# Ethernet.net
KiCad netlist of a schematic drawn in Altium Designer
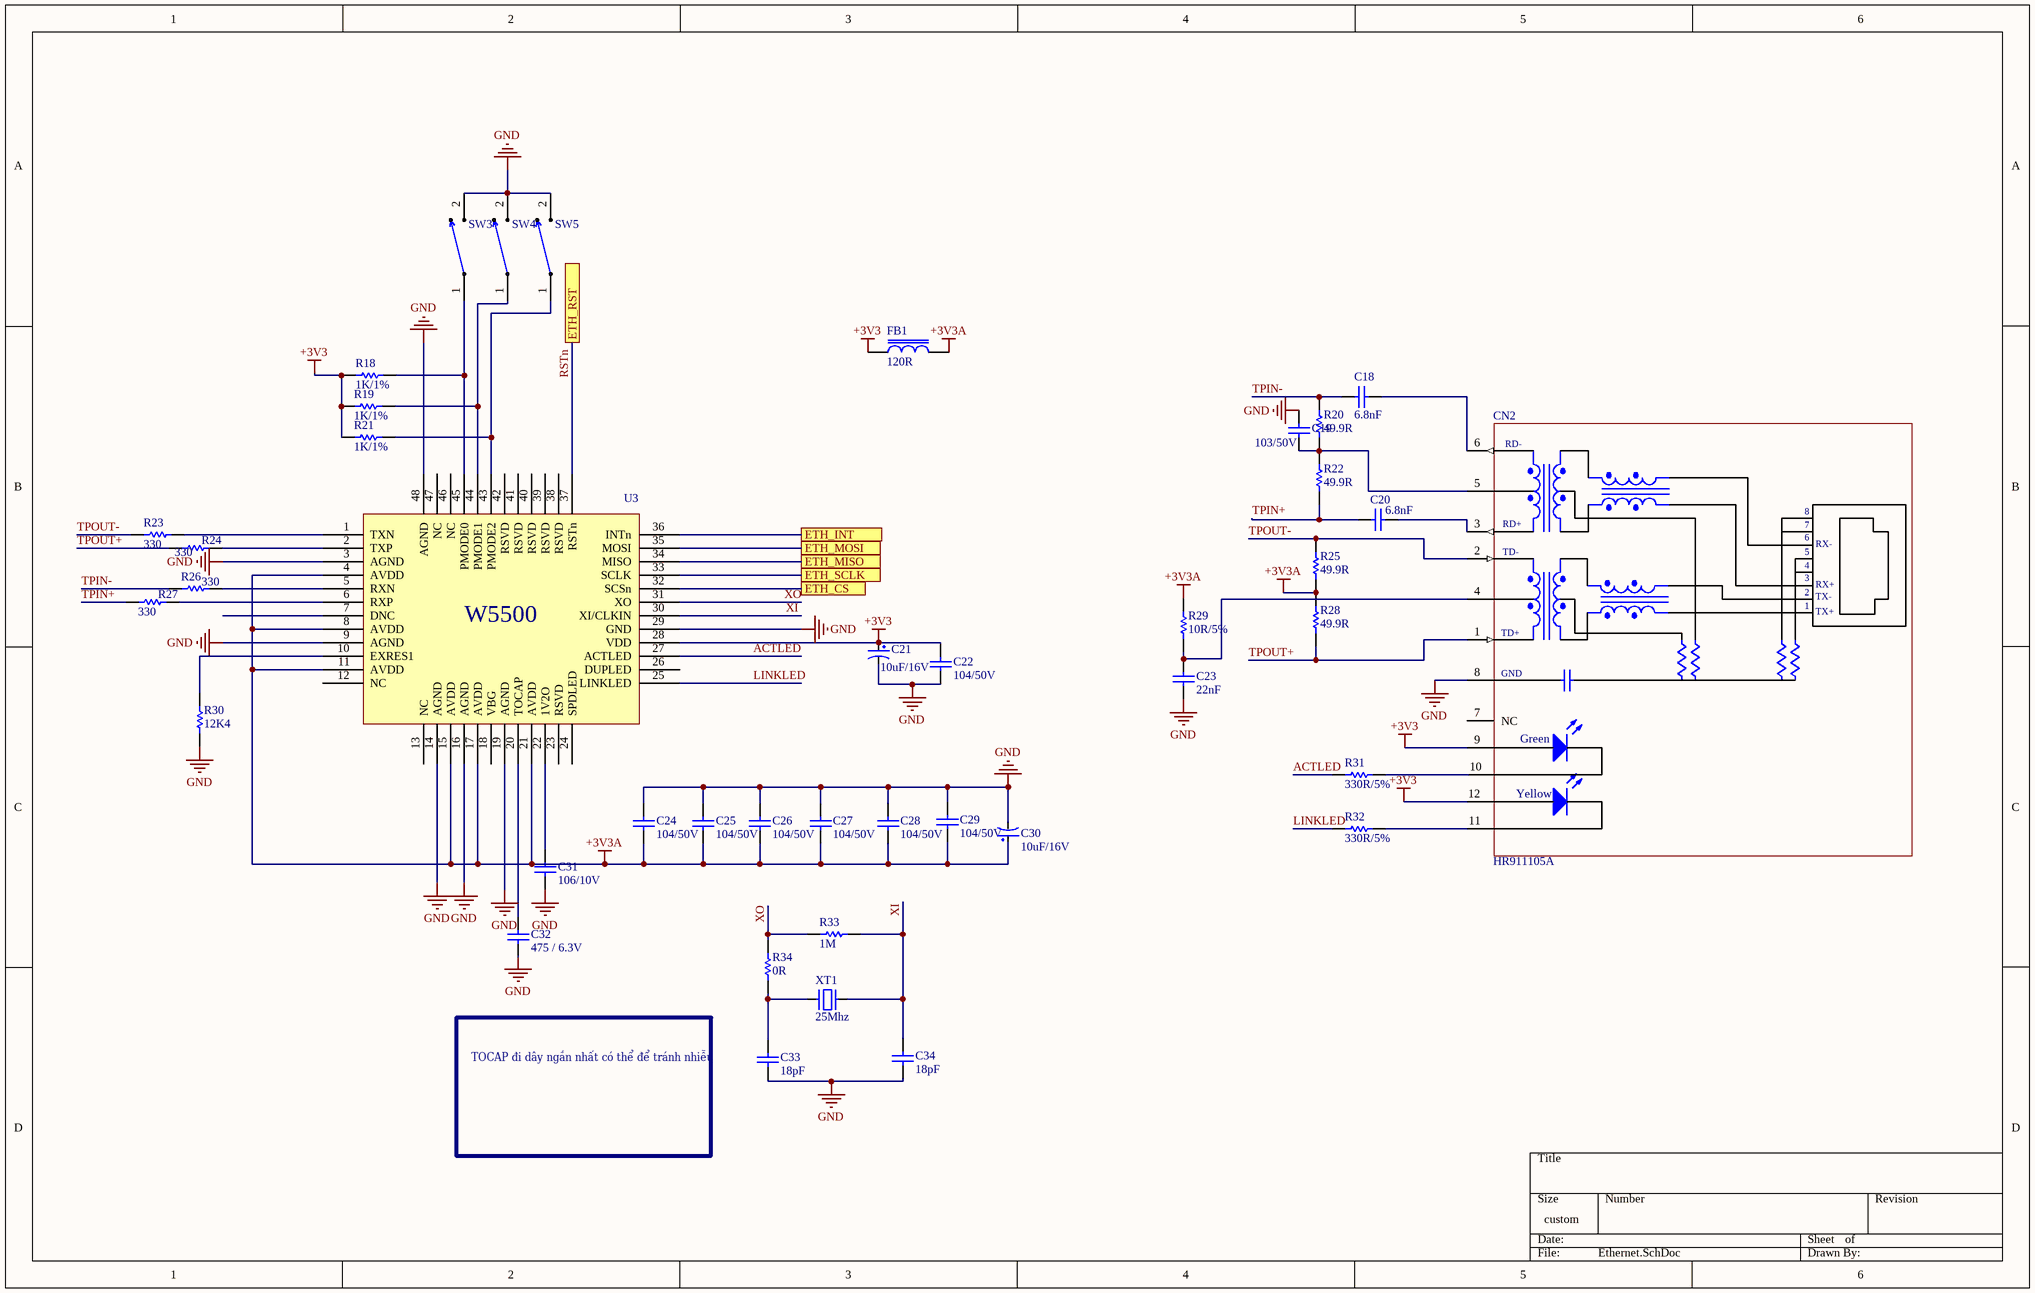
[diagram p0: Ethernet.SchDoc]

(export (version "E")
  (design (tool "Eeschema 10.0.6"))
  (components
    (comp (ref "C18")
      (value "6.8nF")
      (footprint "C0603-B")
      (description "50V 68nF X7R ±10% 0603 Multilayer Ceramic Capacitors MLCC - SMD/SMT ROHS")
      (fields
        (field (name "PARTNUMBER") "CL10B683KB8NNNC")
        (field (name "BSH PARTNUMBER") "C31658")
        (field (name "CREATOR") "Digo")
      )
      (libsource (lib "library-SH") (part "CAP"))
    )
    (comp (ref "C19")
      (value "103/50V")
      (footprint "C0603-B")
      (description "10nF ±10% 50V X7R 0603 Multilayer Ceramic Capacitors MLCC - SMD/SMT RoHS")
      (fields
        (field (name "PARTNUMBER") "CL10B103KB8NNNC")
        (field (name "BSH PARTNUMBER") "C1589")
        (field (name "CREATOR") "Digo")
      )
      (libsource (lib "library-SH") (part "CAP"))
    )
    (comp (ref "C20")
      (value "6.8nF")
      (footprint "C0603-B")
      (description "50V 68nF X7R ±10% 0603 Multilayer Ceramic Capacitors MLCC - SMD/SMT ROHS")
      (fields
        (field (name "PARTNUMBER") "CL10B683KB8NNNC")
        (field (name "BSH PARTNUMBER") "C31658")
        (field (name "CREATOR") "Digo")
      )
      (libsource (lib "library-SH") (part "CAP"))
    )
    (comp (ref "C21")
      (value "10uF/16V")
      (footprint "CAP_3216")
      (description "Polarized Capacitor (Axial)")
      (fields (field (name "PUBLISHER") "Altium Limited"))
      (libsource (lib "My Library") (part "CAP-ALU-SMD"))
    )
    (comp (ref "C22")
      (value "104/50V")
      (footprint "C0603-B")
      (description "100nF ±10% 50V X7R 0603 Multilayer Ceramic Capacitors MLCC - SMD/SMT RoHS")
      (fields
        (field (name "PARTNUMBER") "CL10B104KB8NNNC")
        (field (name "BSH PARTNUMBER") "C1591")
        (field (name "CREATOR") "Digo")
      )
      (libsource (lib "library-SH") (part "CAP"))
    )
    (comp (ref "C23")
      (value "22nF")
      (footprint "C0603-B")
      (description "2.2nF ±10% 50V X7R 0603 Multilayer Ceramic Capacitors MLCC - SMD/SMT RoHS")
      (fields
        (field (name "PARTNUMBER") "CL10B222KB8NNNC")
        (field (name "BSH PARTNUMBER") "C16033")
        (field (name "CREATOR") "Digo")
      )
      (libsource (lib "library-SH") (part "CAP"))
    )
    (comp (ref "C24")
      (value "104/50V")
      (footprint "C0603-B")
      (description "100nF ±10% 50V X7R 0603 Multilayer Ceramic Capacitors MLCC - SMD/SMT RoHS")
      (fields
        (field (name "PARTNUMBER") "CL10B104KB8NNNC")
        (field (name "BSH PARTNUMBER") "C1591")
        (field (name "CREATOR") "Digo")
      )
      (libsource (lib "library-SH") (part "CAP"))
    )
    (comp (ref "C25")
      (value "104/50V")
      (footprint "C0603-B")
      (description "100nF ±10% 50V X7R 0603 Multilayer Ceramic Capacitors MLCC - SMD/SMT RoHS")
      (fields
        (field (name "PARTNUMBER") "CL10B104KB8NNNC")
        (field (name "BSH PARTNUMBER") "C1591")
        (field (name "CREATOR") "Digo")
      )
      (libsource (lib "library-SH") (part "CAP"))
    )
    (comp (ref "C26")
      (value "104/50V")
      (footprint "C0603-B")
      (description "100nF ±10% 50V X7R 0603 Multilayer Ceramic Capacitors MLCC - SMD/SMT RoHS")
      (fields
        (field (name "PARTNUMBER") "CL10B104KB8NNNC")
        (field (name "BSH PARTNUMBER") "C1591")
        (field (name "CREATOR") "Digo")
      )
      (libsource (lib "library-SH") (part "CAP"))
    )
    (comp (ref "C27")
      (value "104/50V")
      (footprint "C0603-B")
      (description "100nF ±10% 50V X7R 0603 Multilayer Ceramic Capacitors MLCC - SMD/SMT RoHS")
      (fields
        (field (name "PARTNUMBER") "CL10B104KB8NNNC")
        (field (name "BSH PARTNUMBER") "C1591")
        (field (name "CREATOR") "Digo")
      )
      (libsource (lib "library-SH") (part "CAP"))
    )
    (comp (ref "C28")
      (value "104/50V")
      (footprint "C0603-B")
      (description "100nF ±10% 50V X7R 0603 Multilayer Ceramic Capacitors MLCC - SMD/SMT RoHS")
      (fields
        (field (name "PARTNUMBER") "CL10B104KB8NNNC")
        (field (name "BSH PARTNUMBER") "C1591")
        (field (name "CREATOR") "Digo")
      )
      (libsource (lib "library-SH") (part "CAP"))
    )
    (comp (ref "C29")
      (value "104/50V")
      (footprint "C0603-B")
      (description "100nF ±10% 50V X7R 0603 Multilayer Ceramic Capacitors MLCC - SMD/SMT RoHS")
      (fields
        (field (name "PARTNUMBER") "CL10B104KB8NNNC")
        (field (name "BSH PARTNUMBER") "C1591")
        (field (name "CREATOR") "Digo")
      )
      (libsource (lib "library-SH") (part "CAP"))
    )
    (comp (ref "C30")
      (value "10uF/16V")
      (footprint "CAP_3216")
      (description "Polarized Capacitor (Axial)")
      (fields (field (name "PUBLISHER") "Altium Limited"))
      (libsource (lib "My Library") (part "CAP-ALU-SMD"))
    )
    (comp (ref "C31")
      (value "106/10V")
      (footprint "C0603-B")
      (description "10uF ±10% 10V X5R 0603 Multilayer Ceramic Capacitors MLCC - SMD/SMT RoHS")
      (fields
        (field (name "PARTNUMBER") "CL10A106KP8NNNC")
        (field (name "BSH PARTNUMBER") "C19702")
        (field (name "CREATOR") "Digo")
      )
      (libsource (lib "library-SH") (part "CAP"))
    )
    (comp (ref "C32")
      (value "475 / 6.3V")
      (footprint "C0603-B")
      (description "Multilayer Ceramic Capacitors MLCC - SMD/SMT 4.7uF+/-20% 6.3V X5R 1608")
      (fields
        (field (name "PARTNUMBER") "CL10A475MQ8NNNC")
        (field (name "BSH PARTNUMBER") "New part")
        (field (name "CREATOR") "NamNH")
      )
      (libsource (lib "library-SH") (part "CAP"))
    )
    (comp (ref "C33")
      (value "18pF")
      (footprint "C0603-B")
      (description "10uF ±10% 10V X5R 0603 Multilayer Ceramic Capacitors MLCC - SMD/SMT RoHS")
      (fields
        (field (name "PARTNUMBER") "CL10A106KP8NNNC")
        (field (name "BSH PARTNUMBER") "C19702")
        (field (name "CREATOR") "Digo")
      )
      (libsource (lib "library-SH") (part "CAP"))
    )
    (comp (ref "C34")
      (value "18pF")
      (footprint "C0603-B")
      (description "10uF ±10% 10V X5R 0603 Multilayer Ceramic Capacitors MLCC - SMD/SMT RoHS")
      (fields
        (field (name "PARTNUMBER") "CL10A106KP8NNNC")
        (field (name "BSH PARTNUMBER") "C19702")
        (field (name "CREATOR") "Digo")
      )
      (libsource (lib "library-SH") (part "CAP"))
    )
    (comp (ref "CN2")
      (value "HR911105A")
      (footprint "HR911105A")
      (description "CON  RJ45  with Magnetics & LED")
      (fields (field (name "BSH PARTNUMBER") "CN-HR911105A") (field (name "CREATOR") "ChienNQ"))
      (libsource (lib "library-SH") (part "HR911105A"))
    )
    (comp (ref "FB1")
      (value "120R")
      (footprint "FB0805-B")
      (description "2A 1 200mΩ 300Ω 100MHz 0805 Ferrite Beads ROHS")
      (fields
        (field (name "PARTNUMBER") "CBW201209U301T")
        (field (name "BSH PARTNUMBER") "C67451")
        (field (name "CREATOR") "Digo")
      )
      (libsource (lib "library-SH") (part "FB"))
    )
    (comp (ref "R18")
      (value "1K/1%")
      (footprint "R0603-B")
      (description "RES 0603 1K 1% 100mW")
      (fields
        (field (name "PARTNUMBER") "RC0603FR-071KL")
        (field (name "BSH PARTNUMBER") "R-1k-0603-1")
        (field (name "CREATOR") "SmartDevice")
      )
      (libsource (lib "library-SH") (part "RES"))
    )
    (comp (ref "R19")
      (value "1K/1%")
      (footprint "R0603-B")
      (description "RES 0603 1K 1% 100mW")
      (fields
        (field (name "PARTNUMBER") "RC0603FR-071KL")
        (field (name "BSH PARTNUMBER") "R-1k-0603-1")
        (field (name "CREATOR") "SmartDevice")
      )
      (libsource (lib "library-SH") (part "RES"))
    )
    (comp (ref "R20")
      (value "49.9R")
      (footprint "R0603-B")
      (description "RES 0603 10K 1% 100mW")
      (fields
        (field (name "PARTNUMBER") "RC0603FR-0710KL")
        (field (name "BSH PARTNUMBER") "C98220")
        (field (name "CREATOR") "Digo")
      )
      (libsource (lib "library-SH") (part "RES"))
    )
    (comp (ref "R21")
      (value "1K/1%")
      (footprint "R0603-B")
      (description "RES 0603 1K 1% 100mW")
      (fields
        (field (name "PARTNUMBER") "RC0603FR-071KL")
        (field (name "BSH PARTNUMBER") "R-1k-0603-1")
        (field (name "CREATOR") "SmartDevice")
      )
      (libsource (lib "library-SH") (part "RES"))
    )
    (comp (ref "R22")
      (value "49.9R")
      (footprint "R0603-B")
      (description "RES 0603 10K 1% 100mW")
      (fields
        (field (name "PARTNUMBER") "RC0603FR-0710KL")
        (field (name "BSH PARTNUMBER") "C98220")
        (field (name "CREATOR") "Digo")
      )
      (libsource (lib "library-SH") (part "RES"))
    )
    (comp (ref "R23")
      (value "330")
      (footprint "R0603-B")
      (description "RES 0603 33R 5% 100mW")
      (fields
        (field (name "PARTNUMBER") "RC0603JR-0733RL")
        (field (name "BSH PARTNUMBER") "R-33R-0603-5")
        (field (name "CREATOR") "ChienNQ")
      )
      (libsource (lib "library-SH") (part "RES"))
    )
    (comp (ref "R24")
      (value "330")
      (footprint "R0603-B")
      (description "RES 0603 33R 5% 100mW")
      (fields
        (field (name "PARTNUMBER") "RC0603JR-0733RL")
        (field (name "BSH PARTNUMBER") "R-33R-0603-5")
        (field (name "CREATOR") "ChienNQ")
      )
      (libsource (lib "library-SH") (part "RES"))
    )
    (comp (ref "R25")
      (value "49.9R")
      (footprint "R0603-B")
      (description "RES 0603 10K 1% 100mW")
      (fields
        (field (name "PARTNUMBER") "RC0603FR-0710KL")
        (field (name "BSH PARTNUMBER") "C98220")
        (field (name "CREATOR") "Digo")
      )
      (libsource (lib "library-SH") (part "RES"))
    )
    (comp (ref "R26")
      (value "330")
      (footprint "R0603-B")
      (description "RES 0603 33R 5% 100mW")
      (fields
        (field (name "PARTNUMBER") "RC0603JR-0733RL")
        (field (name "BSH PARTNUMBER") "R-33R-0603-5")
        (field (name "CREATOR") "ChienNQ")
      )
      (libsource (lib "library-SH") (part "RES"))
    )
    (comp (ref "R27")
      (value "330")
      (footprint "R0603-B")
      (description "RES 0603 33R 5% 100mW")
      (fields
        (field (name "PARTNUMBER") "RC0603JR-0733RL")
        (field (name "BSH PARTNUMBER") "R-33R-0603-5")
        (field (name "CREATOR") "ChienNQ")
      )
      (libsource (lib "library-SH") (part "RES"))
    )
    (comp (ref "R28")
      (value "49.9R")
      (footprint "R0603-B")
      (description "RES 0603 10K 1% 100mW")
      (fields
        (field (name "PARTNUMBER") "RC0603FR-0710KL")
        (field (name "BSH PARTNUMBER") "C98220")
        (field (name "CREATOR") "Digo")
      )
      (libsource (lib "library-SH") (part "RES"))
    )
    (comp (ref "R29")
      (value "10R/5%")
      (footprint "R0603-B")
      (description "RES 0603 10R 5% 100mW")
      (fields
        (field (name "PARTNUMBER") "RC0603JR-0710RL")
        (field (name "BSH PARTNUMBER") "C109317")
        (field (name "CREATOR") "Digo")
      )
      (libsource (lib "library-SH") (part "RES"))
    )
    (comp (ref "R30")
      (value "12K4")
      (footprint "R0603-B")
      (description "RES 0603 12.4K 1% 100mW")
      (fields
        (field (name "PARTNUMBER") "RC0603FR-0712K4L")
        (field (name "BSH PARTNUMBER") "R-12K4-0603-1")
        (field (name "CREATOR") "ChienNQ")
      )
      (libsource (lib "library-SH") (part "RES"))
    )
    (comp (ref "R31")
      (value "330R/5%")
      (footprint "R0603-B")
      (description "RES 0603 330R 5% 100mW")
      (fields
        (field (name "PARTNUMBER") "RC0603JR-07330RL")
        (field (name "BSH PARTNUMBER") "R-330R-0603-5")
        (field (name "CREATOR") "SmartDevice")
      )
      (libsource (lib "library-SH") (part "RES"))
    )
    (comp (ref "R32")
      (value "330R/5%")
      (footprint "R0603-B")
      (description "RES 0603 330R 5% 100mW")
      (fields
        (field (name "PARTNUMBER") "RC0603JR-07330RL")
        (field (name "BSH PARTNUMBER") "R-330R-0603-5")
        (field (name "CREATOR") "SmartDevice")
      )
      (libsource (lib "library-SH") (part "RES"))
    )
    (comp (ref "R33")
      (value "1M")
      (footprint "R0603-B")
      (description "RES 0603 2M 5% 100mW")
      (fields
        (field (name "PARTNUMBER") "RC0603JR-072ML")
        (field (name "BSH PARTNUMBER") "R-2M-0603-5")
        (field (name "CREATOR") "NamNHc")
      )
      (libsource (lib "library-SH") (part "RES"))
    )
    (comp (ref "R34")
      (value "0R")
      (footprint "R0603-B")
      (description "RES 0603 0R 5% 100mW")
      (fields
        (field (name "PARTNUMBER") "RC0603JR-070RL")
        (field (name "BSH PARTNUMBER") "C95177")
        (field (name "CREATOR") "Digo")
      )
      (libsource (lib "library-SH") (part "RES"))
    )
    (comp (ref "SW3")
      (value "Switch NO")
      (footprint "SW0.5 NO")
      (fields
        (field (name "PARTNUMBER") "PCB Switch NO")
        (field (name "BSH PARTNUMBER") "New part")
        (field (name "CREATOR") "NamNH")
      )
      (libsource (lib "library-SH") (part "Switch NO"))
    )
    (comp (ref "SW4")
      (value "Switch NO")
      (footprint "SW0.5 NO")
      (fields
        (field (name "PARTNUMBER") "PCB Switch NO")
        (field (name "BSH PARTNUMBER") "New part")
        (field (name "CREATOR") "NamNH")
      )
      (libsource (lib "library-SH") (part "Switch NO"))
    )
    (comp (ref "SW5")
      (value "Switch NO")
      (footprint "SW0.5 NO")
      (fields
        (field (name "PARTNUMBER") "PCB Switch NO")
        (field (name "BSH PARTNUMBER") "New part")
        (field (name "CREATOR") "NamNH")
      )
      (libsource (lib "library-SH") (part "Switch NO"))
    )
    (comp (ref "U3") (value "W5500") (footprint "LQFP 48") (libsource (lib "My Library") (part "W5500")))
    (comp (ref "XT1")
      (value "25Mhz")
      (footprint "XTAL-RU49/4")
      (description "CRYSTAL 12.0000MHZ 18PF SMD")
      (fields
        (field (name "MANUFACTURER") "IQD Frequency Products")
        (field (name "PART NUMBER") "LFXTAL036356REEL")
      )
      (libsource (lib "My Library") (part "XT2_1"))
    )
  )
  (nets
    (net (code "1") (name "+3V3") (class "Default")
      (node (ref "C21") (pin "1") (pinfunction "1_1") (pintype "passive"))
      (node (ref "C22") (pin "2") (pinfunction "2_2") (pintype "passive"))
      (node (ref "CN2") (pin "12") (pinfunction "12_12") (pintype "power_in"))
      (node (ref "CN2") (pin "9") (pinfunction "9_9") (pintype "power_in"))
      (node (ref "FB1") (pin "1") (pinfunction "1_1") (pintype "passive"))
      (node (ref "R18") (pin "1") (pinfunction "1_1") (pintype "passive"))
      (node (ref "R19") (pin "1") (pinfunction "1_1") (pintype "passive"))
      (node (ref "R21") (pin "1") (pinfunction "1_1") (pintype "passive"))
      (node (ref "U3") (pin "28") (pinfunction "VDD_28") (pintype "passive"))
    )
    (net (code "2") (name "+3V3A") (class "Default")
      (node (ref "C24") (pin "1") (pinfunction "1_1") (pintype "passive"))
      (node (ref "C25") (pin "1") (pinfunction "1_1") (pintype "passive"))
      (node (ref "C26") (pin "1") (pinfunction "1_1") (pintype "passive"))
      (node (ref "C27") (pin "1") (pinfunction "1_1") (pintype "passive"))
      (node (ref "C28") (pin "1") (pinfunction "1_1") (pintype "passive"))
      (node (ref "C29") (pin "1") (pinfunction "1_1") (pintype "passive"))
      (node (ref "C30") (pin "1") (pinfunction "1_1") (pintype "passive"))
      (node (ref "FB1") (pin "2") (pinfunction "2_2") (pintype "passive"))
      (node (ref "R25") (pin "2") (pinfunction "2_2") (pintype "passive"))
      (node (ref "R28") (pin "1") (pinfunction "1_1") (pintype "passive"))
      (node (ref "R29") (pin "2") (pinfunction "2_2") (pintype "passive"))
      (node (ref "U3") (pin "11") (pinfunction "AVDD_11") (pintype "passive"))
      (node (ref "U3") (pin "15") (pinfunction "AVDD_15") (pintype "passive"))
      (node (ref "U3") (pin "17") (pinfunction "AVDD_17") (pintype "passive"))
      (node (ref "U3") (pin "21") (pinfunction "AVDD_21") (pintype "passive"))
      (node (ref "U3") (pin "4") (pinfunction "AVDD_4") (pintype "passive"))
      (node (ref "U3") (pin "8") (pinfunction "AVDD_8") (pintype "passive"))
    )
    (net (code "3") (name "/ACTLED") (class "Default")
      (node (ref "R31") (pin "1") (pinfunction "1_1") (pintype "passive"))
      (node (ref "U3") (pin "27") (pinfunction "ACTLED_27") (pintype "passive"))
    )
    (net (code "4") (name "/ETH_CS") (class "Default")
      (node (ref "U3") (pin "32") (pinfunction "SCSn_32") (pintype "passive"))
    )
    (net (code "5") (name "/ETH_INT") (class "Default")
      (node (ref "U3") (pin "36") (pinfunction "INTn_36") (pintype "passive"))
    )
    (net (code "6") (name "/ETH_MISO") (class "Default")
      (node (ref "U3") (pin "34") (pinfunction "MISO_34") (pintype "passive"))
    )
    (net (code "7") (name "/ETH_MOSI") (class "Default")
      (node (ref "U3") (pin "35") (pinfunction "MOSI_35") (pintype "passive"))
    )
    (net (code "8") (name "/ETH_SCLK") (class "Default")
      (node (ref "U3") (pin "33") (pinfunction "SCLK_33") (pintype "passive"))
    )
    (net (code "9") (name "/LINKLED") (class "Default")
      (node (ref "R32") (pin "1") (pinfunction "1_1") (pintype "passive"))
      (node (ref "U3") (pin "25") (pinfunction "LINKLED_25") (pintype "passive"))
    )
    (net (code "10") (name "/RSTn") (class "Default")
      (node (ref "U3") (pin "37") (pinfunction "RSTn_37") (pintype "passive"))
    )
    (net (code "11") (name "/TPIN+") (class "Default")
      (node (ref "C20") (pin "1") (pinfunction "1_1") (pintype "passive"))
      (node (ref "R22") (pin "2") (pinfunction "2_2") (pintype "passive"))
      (node (ref "R27") (pin "1") (pinfunction "1_1") (pintype "passive"))
    )
    (net (code "12") (name "/TPIN-") (class "Default")
      (node (ref "C18") (pin "1") (pinfunction "1_1") (pintype "passive"))
      (node (ref "R20") (pin "1") (pinfunction "1_1") (pintype "passive"))
      (node (ref "R26") (pin "1") (pinfunction "1_1") (pintype "passive"))
    )
    (net (code "13") (name "/TPOUT+") (class "Default")
      (node (ref "CN2") (pin "1") (pinfunction "TD+_1") (pintype "input"))
      (node (ref "R24") (pin "1") (pinfunction "1_1") (pintype "passive"))
      (node (ref "R28") (pin "2") (pinfunction "2_2") (pintype "passive"))
    )
    (net (code "14") (name "/TPOUT-") (class "Default")
      (node (ref "CN2") (pin "2") (pinfunction "TD-_2") (pintype "input"))
      (node (ref "R23") (pin "1") (pinfunction "1_1") (pintype "passive"))
      (node (ref "R25") (pin "1") (pinfunction "1_1") (pintype "passive"))
    )
    (net (code "15") (name "/XI") (class "Default")
      (node (ref "C34") (pin "2") (pinfunction "2_2") (pintype "passive"))
      (node (ref "R33") (pin "1") (pinfunction "1_1") (pintype "passive"))
      (node (ref "U3") (pin "30") (pinfunction "XI/CLKIN_30") (pintype "passive"))
      (node (ref "XT1") (pin "2") (pinfunction "2_2") (pintype "passive"))
    )
    (net (code "16") (name "/XO") (class "Default")
      (node (ref "R33") (pin "2") (pinfunction "2_2") (pintype "passive"))
      (node (ref "R34") (pin "2") (pinfunction "2_2") (pintype "passive"))
      (node (ref "U3") (pin "31") (pinfunction "XO_31") (pintype "passive"))
    )
    (net (code "17") (name "GND") (class "Default")
      (node (ref "C19") (pin "2") (pinfunction "2_2") (pintype "passive"))
      (node (ref "C21") (pin "2") (pinfunction "2_2") (pintype "passive"))
      (node (ref "C22") (pin "1") (pinfunction "1_1") (pintype "passive"))
      (node (ref "C23") (pin "1") (pinfunction "1_1") (pintype "passive"))
      (node (ref "C24") (pin "2") (pinfunction "2_2") (pintype "passive"))
      (node (ref "C25") (pin "2") (pinfunction "2_2") (pintype "passive"))
      (node (ref "C26") (pin "2") (pinfunction "2_2") (pintype "passive"))
      (node (ref "C27") (pin "2") (pinfunction "2_2") (pintype "passive"))
      (node (ref "C28") (pin "2") (pinfunction "2_2") (pintype "passive"))
      (node (ref "C29") (pin "2") (pinfunction "2_2") (pintype "passive"))
      (node (ref "C30") (pin "2") (pinfunction "2_2") (pintype "passive"))
      (node (ref "C31") (pin "1") (pinfunction "1_1") (pintype "passive"))
      (node (ref "C32") (pin "1") (pinfunction "1_1") (pintype "passive"))
      (node (ref "C33") (pin "1") (pinfunction "1_1") (pintype "passive"))
      (node (ref "C34") (pin "1") (pinfunction "1_1") (pintype "passive"))
      (node (ref "CN2") (pin "8") (pinfunction "GND_8") (pintype "power_in"))
      (node (ref "R30") (pin "1") (pinfunction "1_1") (pintype "passive"))
      (node (ref "SW3") (pin "2") (pinfunction "1_2") (pintype "passive"))
      (node (ref "SW4") (pin "2") (pinfunction "1_2") (pintype "passive"))
      (node (ref "SW5") (pin "2") (pinfunction "1_2") (pintype "passive"))
      (node (ref "U3") (pin "14") (pinfunction "AGND_14") (pintype "passive"))
      (node (ref "U3") (pin "16") (pinfunction "AGND_16") (pintype "passive"))
      (node (ref "U3") (pin "19") (pinfunction "AGND_19") (pintype "passive"))
      (node (ref "U3") (pin "29") (pinfunction "GND_29") (pintype "passive"))
      (node (ref "U3") (pin "3") (pinfunction "AGND_3") (pintype "passive"))
      (node (ref "U3") (pin "48") (pinfunction "AGND_48") (pintype "passive"))
      (node (ref "U3") (pin "9") (pinfunction "AGND_9") (pintype "passive"))
    )
    (net (code "18") (name "Net-(C19-Pad1)") (class "Default")
      (node (ref "C19") (pin "1") (pinfunction "1_1") (pintype "passive"))
      (node (ref "CN2") (pin "5") (pintype "passive"))
      (node (ref "R20") (pin "2") (pinfunction "2_2") (pintype "passive"))
      (node (ref "R22") (pin "1") (pinfunction "1_1") (pintype "passive"))
    )
    (net (code "19") (name "Net-(C23-Pad2)") (class "Default")
      (node (ref "C23") (pin "2") (pinfunction "2_2") (pintype "passive"))
      (node (ref "CN2") (pin "4") (pintype "passive"))
      (node (ref "R29") (pin "1") (pinfunction "1_1") (pintype "passive"))
    )
    (net (code "20") (name "Net-(C33-Pad2)") (class "Default")
      (node (ref "C33") (pin "2") (pinfunction "2_2") (pintype "passive"))
      (node (ref "R34") (pin "1") (pinfunction "1_1") (pintype "passive"))
      (node (ref "XT1") (pin "1") (pinfunction "1_1") (pintype "passive"))
    )
    (net (code "21") (name "Net-(CN2-Pad10)") (class "Default")
      (node (ref "CN2") (pin "10") (pinfunction "10_10") (pintype "passive"))
      (node (ref "R31") (pin "2") (pinfunction "2_2") (pintype "passive"))
    )
    (net (code "22") (name "Net-(CN2-Pad11)") (class "Default")
      (node (ref "CN2") (pin "11") (pinfunction "11_11") (pintype "passive"))
      (node (ref "R32") (pin "2") (pinfunction "2_2") (pintype "passive"))
    )
    (net (code "23") (name "Net-(CN2-RD+)") (class "Default")
      (node (ref "C20") (pin "2") (pinfunction "2_2") (pintype "passive"))
      (node (ref "CN2") (pin "3") (pinfunction "RD+_3") (pintype "output"))
    )
    (net (code "24") (name "Net-(CN2-RD-)") (class "Default")
      (node (ref "C18") (pin "2") (pinfunction "2_2") (pintype "passive"))
      (node (ref "CN2") (pin "6") (pinfunction "RD-_6") (pintype "output"))
    )
    (net (code "25") (name "Net-(SW3-0)") (class "Default")
      (node (ref "R18") (pin "2") (pinfunction "2_2") (pintype "passive"))
      (node (ref "SW3") (pin "1") (pinfunction "0_1") (pintype "passive"))
      (node (ref "U3") (pin "45") (pinfunction "PMODE0_45") (pintype "passive"))
    )
    (net (code "26") (name "Net-(SW4-0)") (class "Default")
      (node (ref "R19") (pin "2") (pinfunction "2_2") (pintype "passive"))
      (node (ref "SW4") (pin "1") (pinfunction "0_1") (pintype "passive"))
      (node (ref "U3") (pin "44") (pinfunction "PMODE1_44") (pintype "passive"))
    )
    (net (code "27") (name "Net-(SW5-0)") (class "Default")
      (node (ref "R21") (pin "2") (pinfunction "2_2") (pintype "passive"))
      (node (ref "SW5") (pin "1") (pinfunction "0_1") (pintype "passive"))
      (node (ref "U3") (pin "43") (pinfunction "PMODE2_43") (pintype "passive"))
    )
    (net (code "28") (name "Net-(U3-1V2O)") (class "Default")
      (node (ref "C31") (pin "2") (pinfunction "2_2") (pintype "passive"))
      (node (ref "U3") (pin "22") (pinfunction "1V2O_22") (pintype "passive"))
    )
    (net (code "29") (name "Net-(U3-EXRES1)") (class "Default")
      (node (ref "R30") (pin "2") (pinfunction "2_2") (pintype "passive"))
      (node (ref "U3") (pin "10") (pinfunction "EXRES1_10") (pintype "passive"))
    )
    (net (code "30") (name "Net-(U3-RXN)") (class "Default")
      (node (ref "R26") (pin "2") (pinfunction "2_2") (pintype "passive"))
      (node (ref "U3") (pin "5") (pinfunction "RXN_5") (pintype "passive"))
    )
    (net (code "31") (name "Net-(U3-RXP)") (class "Default")
      (node (ref "R27") (pin "2") (pinfunction "2_2") (pintype "passive"))
      (node (ref "U3") (pin "6") (pinfunction "RXP_6") (pintype "passive"))
    )
    (net (code "32") (name "Net-(U3-TOCAP)") (class "Default")
      (node (ref "C32") (pin "2") (pinfunction "2_2") (pintype "passive"))
      (node (ref "U3") (pin "20") (pinfunction "TOCAP_20") (pintype "passive"))
    )
    (net (code "33") (name "Net-(U3-TXN)") (class "Default")
      (node (ref "R23") (pin "2") (pinfunction "2_2") (pintype "passive"))
      (node (ref "U3") (pin "1") (pinfunction "TXN_1") (pintype "passive"))
    )
    (net (code "34") (name "Net-(U3-TXP)") (class "Default")
      (node (ref "R24") (pin "2") (pinfunction "2_2") (pintype "passive"))
      (node (ref "U3") (pin "2") (pinfunction "TXP_2") (pintype "passive"))
    )
    (net (code "35") (name "unconnected-(CN2-NC-Pad7)") (class "Default")
      (node (ref "CN2") (pin "7") (pinfunction "NC_7") (pintype "passive"))
    )
    (net (code "36") (name "unconnected-(U3-DNC-Pad7)") (class "Default")
      (node (ref "U3") (pin "7") (pinfunction "DNC_7") (pintype "passive"))
    )
    (net (code "37") (name "unconnected-(U3-DUPLED-Pad26)") (class "Default")
      (node (ref "U3") (pin "26") (pinfunction "DUPLED_26") (pintype "passive"))
    )
    (net (code "38") (name "unconnected-(U3-NC-Pad12)") (class "Default")
      (node (ref "U3") (pin "12") (pinfunction "NC_12") (pintype "passive"))
    )
    (net (code "39") (name "unconnected-(U3-NC-Pad13)") (class "Default")
      (node (ref "U3") (pin "13") (pinfunction "NC_13") (pintype "passive"))
    )
    (net (code "40") (name "unconnected-(U3-NC-Pad46)") (class "Default")
      (node (ref "U3") (pin "46") (pinfunction "NC_46") (pintype "passive"))
    )
    (net (code "41") (name "unconnected-(U3-NC-Pad47)") (class "Default")
      (node (ref "U3") (pin "47") (pinfunction "NC_47") (pintype "passive"))
    )
    (net (code "42") (name "unconnected-(U3-RSVD-Pad23)") (class "Default")
      (node (ref "U3") (pin "23") (pinfunction "RSVD_23") (pintype "passive"))
    )
    (net (code "43") (name "unconnected-(U3-RSVD-Pad38)") (class "Default")
      (node (ref "U3") (pin "38") (pinfunction "RSVD_38") (pintype "passive"))
    )
    (net (code "44") (name "unconnected-(U3-RSVD-Pad39)") (class "Default")
      (node (ref "U3") (pin "39") (pinfunction "RSVD_39") (pintype "passive"))
    )
    (net (code "45") (name "unconnected-(U3-RSVD-Pad40)") (class "Default")
      (node (ref "U3") (pin "40") (pinfunction "RSVD_40") (pintype "passive"))
    )
    (net (code "46") (name "unconnected-(U3-RSVD-Pad41)") (class "Default")
      (node (ref "U3") (pin "41") (pinfunction "RSVD_41") (pintype "passive"))
    )
    (net (code "47") (name "unconnected-(U3-RSVD-Pad42)") (class "Default")
      (node (ref "U3") (pin "42") (pinfunction "RSVD_42") (pintype "passive"))
    )
    (net (code "48") (name "unconnected-(U3-SPDLED-Pad24)") (class "Default")
      (node (ref "U3") (pin "24") (pinfunction "SPDLED_24") (pintype "passive"))
    )
    (net (code "49") (name "unconnected-(U3-VBG-Pad18)") (class "Default")
      (node (ref "U3") (pin "18") (pinfunction "VBG_18") (pintype "passive"))
    )
  )
)
